# David_Smith-smd.net
KiCad netlist of a schematic drawn in EAGLE
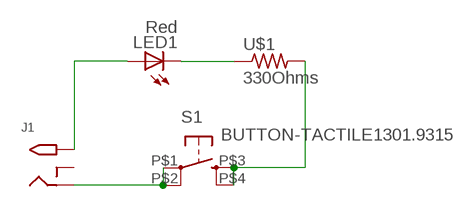
[diagram p0: schematic, sheet 1]

(export (version "E")
  (design (tool "Eeschema 10.0.6"))
  (components
    (comp (ref "J1")
      (value "2.1MMJACKTHM")
      (footprint "eagle-import:PJ-102A")
      (libsource (lib "eagle-import") (part "2.1MMJACKTHM"))
    )
    (comp (ref "LED1")
      (value "Red")
      (footprint "eagle-import:LED5MM")
      (libsource (lib "eagle-import") (part "LED5MM"))
    )
    (comp (ref "S1")
      (value "BUTTON-TACTILE1301.9315")
      (footprint "eagle-import:SMD-BUTTON")
      (libsource (lib "eagle-import") (part "BUTTON-TACTILE1301.9315"))
    )
    (comp (ref "U$1")
      (value "330Ohms")
      (footprint "eagle-import:RESAD1160W55L680D260_HS")
      (libsource (lib "eagle-import") (part "RESISTORTH-1/4W-CARBON"))
    )
  )
  (nets
    (net (code "1") (name "Net-(J1-PadTIP)") (class "Default")
      (node (ref "J1") (pin "TIP") (pinfunction "TIP_TIP") (pintype "bidirectional"))
      (node (ref "LED1") (pin "A") (pinfunction "A_A") (pintype "passive"))
    )
    (net (code "2") (name "Net-(LED1-C)") (class "Default")
      (node (ref "LED1") (pin "K") (pinfunction "C_K") (pintype "passive"))
      (node (ref "U$1") (pin "1") (pinfunction "1_1") (pintype "passive"))
    )
    (net (code "3") (name "Net-(S1-P)") (class "Default")
      (node (ref "J1") (pin "RING") (pinfunction "RING_RING") (pintype "bidirectional"))
      (node (ref "S1") (pin "P$1") (pinfunction "P_P$1") (pintype "passive"))
      (node (ref "S1") (pin "P$2") (pinfunction "P1_P$2") (pintype "passive"))
    )
    (net (code "4") (name "Net-(S1-S)") (class "Default")
      (node (ref "S1") (pin "P$3") (pinfunction "S_P$3") (pintype "passive"))
      (node (ref "S1") (pin "P$4") (pinfunction "S1_P$4") (pintype "passive"))
      (node (ref "U$1") (pin "2") (pinfunction "2_2") (pintype "passive"))
    )
    (net (code "5") (name "unconnected-(J1-PadRING_SW)") (class "Default")
      (node (ref "J1") (pin "RING_SW") (pinfunction "RING_SW_RING_SW") (pintype "bidirectional"))
    )
  )
)
